# W5500.net
KiCad netlist of a schematic drawn in Altium Designer
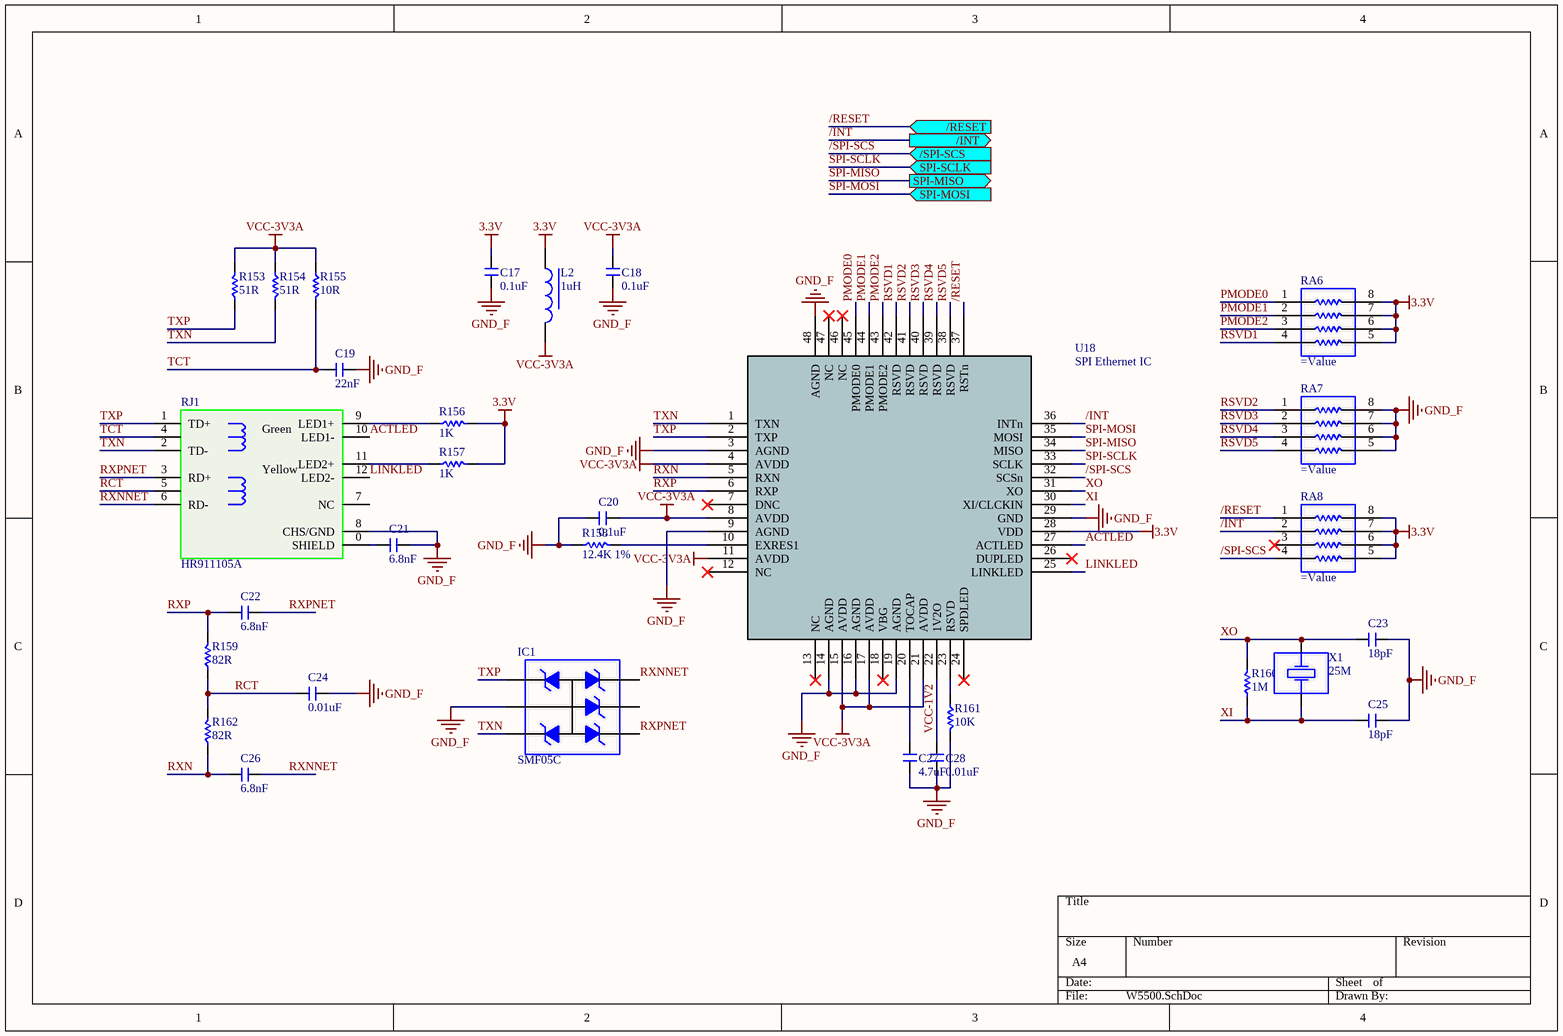
[diagram p0: W5500.SchDoc]

(export (version "E")
  (design (tool "Eeschema 10.0.6"))
  (components
    (comp (ref "C17")
      (value "0.1uF")
      (footprint "C 0805")
      (description "Non-polar patch capacitor")
      (fields (field (name "版权归属") "源创客"))
      (libsource (lib "Passive (Resistor-Capacitor-Inductor-Veristor-Ferrite)") (part "C"))
    )
    (comp (ref "C18")
      (value "0.1uF")
      (footprint "C 0805")
      (description "Non-polar patch capacitor")
      (fields (field (name "版权归属") "源创客"))
      (libsource (lib "Passive (Resistor-Capacitor-Inductor-Veristor-Ferrite)") (part "C"))
    )
    (comp (ref "C19")
      (value "22nF")
      (footprint "C 0805")
      (description "Non-polar patch capacitor")
      (fields (field (name "版权归属") "源创客"))
      (libsource (lib "Passive (Resistor-Capacitor-Inductor-Veristor-Ferrite)") (part "C"))
    )
    (comp (ref "C20")
      (value "0.1uF")
      (footprint "C 0805")
      (description "Non-polar patch capacitor")
      (fields (field (name "版权归属") "源创客"))
      (libsource (lib "Passive (Resistor-Capacitor-Inductor-Veristor-Ferrite)") (part "C"))
    )
    (comp (ref "C21")
      (value "6.8nF")
      (footprint "C 0805")
      (description "Non-polar patch capacitor")
      (fields (field (name "版权归属") "源创客"))
      (libsource (lib "Passive (Resistor-Capacitor-Inductor-Veristor-Ferrite)") (part "C"))
    )
    (comp (ref "C22")
      (value "6.8nF")
      (footprint "C 0805")
      (description "Non-polar patch capacitor")
      (fields (field (name "版权归属") "源创客"))
      (libsource (lib "Passive (Resistor-Capacitor-Inductor-Veristor-Ferrite)") (part "C"))
    )
    (comp (ref "C23")
      (value "18pF")
      (footprint "C 0805")
      (description "Non-polar patch capacitor")
      (fields (field (name "版权归属") "源创客"))
      (libsource (lib "Passive (Resistor-Capacitor-Inductor-Veristor-Ferrite)") (part "C"))
    )
    (comp (ref "C24")
      (value "0.01uF")
      (footprint "C 0805")
      (description "Non-polar patch capacitor")
      (fields (field (name "版权归属") "源创客"))
      (libsource (lib "Passive (Resistor-Capacitor-Inductor-Veristor-Ferrite)") (part "C"))
    )
    (comp (ref "C25")
      (value "18pF")
      (footprint "C 0805")
      (description "Non-polar patch capacitor")
      (fields (field (name "版权归属") "源创客"))
      (libsource (lib "Passive (Resistor-Capacitor-Inductor-Veristor-Ferrite)") (part "C"))
    )
    (comp (ref "C26")
      (value "6.8nF")
      (footprint "C 0805")
      (description "Non-polar patch capacitor")
      (fields (field (name "版权归属") "源创客"))
      (libsource (lib "Passive (Resistor-Capacitor-Inductor-Veristor-Ferrite)") (part "C"))
    )
    (comp (ref "C27")
      (value "4.7uF")
      (footprint "C 0805")
      (description "Non-polar patch capacitor")
      (fields (field (name "版权归属") "源创客"))
      (libsource (lib "Passive (Resistor-Capacitor-Inductor-Veristor-Ferrite)") (part "C"))
    )
    (comp (ref "C28")
      (value "0.01uF")
      (footprint "C 0805")
      (description "Non-polar patch capacitor")
      (fields (field (name "版权归属") "源创客"))
      (libsource (lib "Passive (Resistor-Capacitor-Inductor-Veristor-Ferrite)") (part "C"))
    )
    (comp (ref "IC1")
      (value "SMF05C")
      (footprint "SOT23-6L")
      (description "ESD Protection Diode Array, 5-Line")
      (libsource (lib "Diode-Zener-Rectifier Bridge") (part "SMF05C"))
    )
    (comp (ref "L2")
      (value "1uH")
      (footprint "L 0805")
      (description "Low power chip inductor")
      (fields (field (name "版权归属") "源创客"))
      (libsource (lib "Passive (Resistor-Capacitor-Inductor-Veristor-Ferrite)") (part "L"))
    )
    (comp (ref "R153")
      (value "51R")
      (footprint "R 0805")
      (description "Chip resistor")
      (fields (field (name "版权归属") "源创客"))
      (libsource (lib "Passive (Resistor-Capacitor-Inductor-Veristor-Ferrite)") (part "R"))
    )
    (comp (ref "R154")
      (value "51R")
      (footprint "R 0805")
      (description "Chip resistor")
      (fields (field (name "版权归属") "源创客"))
      (libsource (lib "Passive (Resistor-Capacitor-Inductor-Veristor-Ferrite)") (part "R"))
    )
    (comp (ref "R155")
      (value "10R")
      (footprint "R 0805")
      (description "Chip resistor")
      (fields (field (name "版权归属") "源创客"))
      (libsource (lib "Passive (Resistor-Capacitor-Inductor-Veristor-Ferrite)") (part "R"))
    )
    (comp (ref "R156")
      (value "1K")
      (footprint "R 0805")
      (description "Chip resistor")
      (fields (field (name "版权归属") "源创客"))
      (libsource (lib "Passive (Resistor-Capacitor-Inductor-Veristor-Ferrite)") (part "R"))
    )
    (comp (ref "R157")
      (value "1K")
      (footprint "R 0805")
      (description "Chip resistor")
      (fields (field (name "版权归属") "源创客"))
      (libsource (lib "Passive (Resistor-Capacitor-Inductor-Veristor-Ferrite)") (part "R"))
    )
    (comp (ref "R158")
      (value "12.4K 1%")
      (footprint "R 0805")
      (description "Chip resistor")
      (fields (field (name "版权归属") "源创客"))
      (libsource (lib "Passive (Resistor-Capacitor-Inductor-Veristor-Ferrite)") (part "R"))
    )
    (comp (ref "R159")
      (value "82R")
      (footprint "R 0805")
      (description "Chip resistor")
      (fields (field (name "版权归属") "源创客"))
      (libsource (lib "Passive (Resistor-Capacitor-Inductor-Veristor-Ferrite)") (part "R"))
    )
    (comp (ref "R160")
      (value "1M")
      (footprint "R 0805")
      (description "Chip resistor")
      (fields (field (name "版权归属") "源创客"))
      (libsource (lib "Passive (Resistor-Capacitor-Inductor-Veristor-Ferrite)") (part "R"))
    )
    (comp (ref "R161")
      (value "10K")
      (footprint "R 0805")
      (description "Chip resistor")
      (fields (field (name "版权归属") "源创客"))
      (libsource (lib "Passive (Resistor-Capacitor-Inductor-Veristor-Ferrite)") (part "R"))
    )
    (comp (ref "R162")
      (value "82R")
      (footprint "R 0805")
      (description "Chip resistor")
      (fields (field (name "版权归属") "源创客"))
      (libsource (lib "Passive (Resistor-Capacitor-Inductor-Veristor-Ferrite)") (part "R"))
    )
    (comp (ref "RA6")
      (value "~")
      (footprint "RA1206 (4x0603)")
      (description "4 way Chip Resistor Array")
      (libsource (lib "Passive (Resistor-Capacitor-Inductor-Veristor-Ferrite)") (part "R-ARR"))
    )
    (comp (ref "RA7")
      (value "~")
      (footprint "RA1206 (4x0603)")
      (description "4 way Chip Resistor Array")
      (libsource (lib "Passive (Resistor-Capacitor-Inductor-Veristor-Ferrite)") (part "R-ARR"))
    )
    (comp (ref "RA8")
      (value "~")
      (footprint "RA1206 (4x0603)")
      (description "4 way Chip Resistor Array")
      (libsource (lib "Passive (Resistor-Capacitor-Inductor-Veristor-Ferrite)") (part "R-ARR"))
    )
    (comp (ref "RJ1")
      (value "HR911105A")
      (footprint "RJ-45A12")
      (description "Illuminated Ethernet interface")
      (fields (field (name "版权归属") "源创客"))
      (libsource (lib "IO (Power-USB-Serial-VGA-RJ-Audio-Buzzer)") (part "HR911105A"))
    )
    (comp (ref "U18")
      (value "SPI Ethernet IC")
      (footprint "LQFP48 7X7_L")
      (libsource (lib "Integrated Circuit") (part "W5500"))
    )
    (comp (ref "X1")
      (value "25M")
      (footprint "XTAL-HC49S-THD")
      (description "2-Pin crystal")
      (fields (field (name "版权归属") "源创客"))
      (libsource (lib "Crystal Oscillator") (part "XTAL-2"))
    )
  )
  (nets
    (net (code "1") (name "/ACTLED") (class "Default")
      (node (ref "RJ1") (pin "10") (pinfunction "LED1-_10") (pintype "passive"))
      (node (ref "U18") (pin "27") (pinfunction "ACTLED_27") (pintype "passive"))
    )
    (net (code "2") (name "/LINKLED") (class "Default")
      (node (ref "RJ1") (pin "12") (pinfunction "LED2-_12") (pintype "passive"))
      (node (ref "U18") (pin "25") (pinfunction "LINKLED_25") (pintype "passive"))
    )
    (net (code "3") (name "/PMODE0") (class "Default")
      (node (ref "RA6") (pin "1") (pinfunction "1_1") (pintype "passive"))
      (node (ref "U18") (pin "45") (pinfunction "PMODE0_45") (pintype "passive"))
    )
    (net (code "4") (name "/PMODE1") (class "Default")
      (node (ref "RA6") (pin "2") (pinfunction "2_2") (pintype "passive"))
      (node (ref "U18") (pin "44") (pinfunction "PMODE1_44") (pintype "passive"))
    )
    (net (code "5") (name "/PMODE2") (class "Default")
      (node (ref "RA6") (pin "3") (pinfunction "3_3") (pintype "passive"))
      (node (ref "U18") (pin "43") (pinfunction "PMODE2_43") (pintype "passive"))
    )
    (net (code "6") (name "/RCT") (class "Default")
      (node (ref "C24") (pin "1") (pinfunction "1_1") (pintype "passive"))
      (node (ref "R159") (pin "1") (pinfunction "1_1") (pintype "passive"))
      (node (ref "R162") (pin "2") (pinfunction "2_2") (pintype "passive"))
      (node (ref "RJ1") (pin "5") (pintype "passive"))
    )
    (net (code "7") (name "/RSVD1") (class "Default")
      (node (ref "RA6") (pin "4") (pinfunction "4_4") (pintype "passive"))
      (node (ref "U18") (pin "42") (pinfunction "RSVD_42") (pintype "passive"))
    )
    (net (code "8") (name "/RSVD2") (class "Default")
      (node (ref "RA7") (pin "1") (pinfunction "1_1") (pintype "passive"))
      (node (ref "U18") (pin "41") (pinfunction "RSVD_41") (pintype "passive"))
    )
    (net (code "9") (name "/RSVD3") (class "Default")
      (node (ref "RA7") (pin "2") (pinfunction "2_2") (pintype "passive"))
      (node (ref "U18") (pin "40") (pinfunction "RSVD_40") (pintype "passive"))
    )
    (net (code "10") (name "/RSVD4") (class "Default")
      (node (ref "RA7") (pin "3") (pinfunction "3_3") (pintype "passive"))
      (node (ref "U18") (pin "39") (pinfunction "RSVD_39") (pintype "passive"))
    )
    (net (code "11") (name "/RSVD5") (class "Default")
      (node (ref "RA7") (pin "4") (pinfunction "4_4") (pintype "passive"))
      (node (ref "U18") (pin "38") (pinfunction "RSVD_38") (pintype "passive"))
    )
    (net (code "12") (name "/RXN") (class "Default")
      (node (ref "C26") (pin "1") (pinfunction "1_1") (pintype "passive"))
      (node (ref "R162") (pin "1") (pinfunction "1_1") (pintype "passive"))
      (node (ref "U18") (pin "5") (pinfunction "RXN_5") (pintype "passive"))
    )
    (net (code "13") (name "/RXNNET") (class "Default")
      (node (ref "C26") (pin "2") (pinfunction "2_2") (pintype "passive"))
      (node (ref "IC1") (pin "4") (pinfunction "K_4") (pintype "passive"))
      (node (ref "RJ1") (pin "6") (pinfunction "RD-_6") (pintype "passive"))
    )
    (net (code "14") (name "/RXP") (class "Default")
      (node (ref "C22") (pin "1") (pinfunction "1_1") (pintype "passive"))
      (node (ref "R159") (pin "2") (pinfunction "2_2") (pintype "passive"))
      (node (ref "U18") (pin "6") (pinfunction "RXP_6") (pintype "passive"))
    )
    (net (code "15") (name "/RXPNET") (class "Default")
      (node (ref "C22") (pin "2") (pinfunction "2_2") (pintype "passive"))
      (node (ref "IC1") (pin "6") (pinfunction "K_6") (pintype "passive"))
      (node (ref "RJ1") (pin "3") (pinfunction "RD+_3") (pintype "passive"))
    )
    (net (code "16") (name "/SPI-MISO") (class "Default")
      (node (ref "U18") (pin "34") (pinfunction "MISO_34") (pintype "passive"))
    )
    (net (code "17") (name "/SPI-MOSI") (class "Default")
      (node (ref "U18") (pin "35") (pinfunction "MOSI_35") (pintype "passive"))
    )
    (net (code "18") (name "/SPI-SCLK") (class "Default")
      (node (ref "U18") (pin "33") (pinfunction "SCLK_33") (pintype "passive"))
    )
    (net (code "19") (name "/TCT") (class "Default")
      (node (ref "C19") (pin "1") (pinfunction "1_1") (pintype "passive"))
      (node (ref "R155") (pin "2") (pinfunction "2_2") (pintype "passive"))
      (node (ref "RJ1") (pin "4") (pintype "passive"))
    )
    (net (code "20") (name "/TXN") (class "Default")
      (node (ref "IC1") (pin "3") (pinfunction "K_3") (pintype "passive"))
      (node (ref "R154") (pin "2") (pinfunction "2_2") (pintype "passive"))
      (node (ref "RJ1") (pin "2") (pinfunction "TD-_2") (pintype "passive"))
      (node (ref "U18") (pin "1") (pinfunction "TXN_1") (pintype "passive"))
    )
    (net (code "21") (name "/TXP") (class "Default")
      (node (ref "IC1") (pin "1") (pinfunction "K_1") (pintype "passive"))
      (node (ref "R153") (pin "1") (pinfunction "1_1") (pintype "passive"))
      (node (ref "RJ1") (pin "1") (pinfunction "TD+_1") (pintype "passive"))
      (node (ref "U18") (pin "2") (pinfunction "TXP_2") (pintype "passive"))
    )
    (net (code "22") (name "/VCC-1V2") (class "Default")
      (node (ref "C28") (pin "1") (pinfunction "1_1") (pintype "passive"))
      (node (ref "U18") (pin "22") (pinfunction "1V2O_22") (pintype "passive"))
    )
    (net (code "23") (name "/XI") (class "Default")
      (node (ref "C25") (pin "1") (pinfunction "1_1") (pintype "passive"))
      (node (ref "R160") (pin "1") (pinfunction "1_1") (pintype "passive"))
      (node (ref "U18") (pin "30") (pinfunction "XI/CLCKIN_30") (pintype "passive"))
      (node (ref "X1") (pin "1") (pinfunction "1_1") (pintype "passive"))
    )
    (net (code "24") (name "/XO") (class "Default")
      (node (ref "C23") (pin "1") (pinfunction "1_1") (pintype "passive"))
      (node (ref "R160") (pin "2") (pinfunction "2_2") (pintype "passive"))
      (node (ref "U18") (pin "31") (pinfunction "XO_31") (pintype "passive"))
      (node (ref "X1") (pin "2") (pinfunction "3_2") (pintype "passive"))
    )
    (net (code "25") (name "/{slash}INT") (class "Default")
      (node (ref "RA8") (pin "2") (pinfunction "2_2") (pintype "passive"))
      (node (ref "U18") (pin "36") (pinfunction "INTn_36") (pintype "passive"))
    )
    (net (code "26") (name "/{slash}RESET") (class "Default")
      (node (ref "RA8") (pin "1") (pinfunction "1_1") (pintype "passive"))
      (node (ref "U18") (pin "37") (pinfunction "RSTn_37") (pintype "passive"))
    )
    (net (code "27") (name "/{slash}SPI-SCS") (class "Default")
      (node (ref "RA8") (pin "4") (pinfunction "4_4") (pintype "passive"))
      (node (ref "U18") (pin "32") (pinfunction "SCSn_32") (pintype "passive"))
    )
    (net (code "28") (name "3.3V") (class "Default")
      (node (ref "C17") (pin "2") (pinfunction "2_2") (pintype "passive"))
      (node (ref "L2") (pin "1") (pinfunction "1_1") (pintype "passive"))
      (node (ref "R156") (pin "2") (pinfunction "2_2") (pintype "passive"))
      (node (ref "R157") (pin "2") (pinfunction "2_2") (pintype "passive"))
      (node (ref "RA6") (pin "5") (pinfunction "5_5") (pintype "passive"))
      (node (ref "RA6") (pin "6") (pinfunction "6_6") (pintype "passive"))
      (node (ref "RA6") (pin "7") (pinfunction "7_7") (pintype "passive"))
      (node (ref "RA6") (pin "8") (pinfunction "8_8") (pintype "passive"))
      (node (ref "RA8") (pin "5") (pinfunction "5_5") (pintype "passive"))
      (node (ref "RA8") (pin "6") (pinfunction "6_6") (pintype "passive"))
      (node (ref "RA8") (pin "7") (pinfunction "7_7") (pintype "passive"))
      (node (ref "RA8") (pin "8") (pinfunction "8_8") (pintype "passive"))
      (node (ref "U18") (pin "28") (pinfunction "VDD_28") (pintype "passive"))
    )
    (net (code "29") (name "GND_F") (class "Default")
      (node (ref "C17") (pin "1") (pinfunction "1_1") (pintype "passive"))
      (node (ref "C18") (pin "1") (pinfunction "1_1") (pintype "passive"))
      (node (ref "C19") (pin "2") (pinfunction "2_2") (pintype "passive"))
      (node (ref "C20") (pin "1") (pinfunction "1_1") (pintype "passive"))
      (node (ref "C21") (pin "2") (pinfunction "2_2") (pintype "passive"))
      (node (ref "C23") (pin "2") (pinfunction "2_2") (pintype "passive"))
      (node (ref "C24") (pin "2") (pinfunction "2_2") (pintype "passive"))
      (node (ref "C25") (pin "2") (pinfunction "2_2") (pintype "passive"))
      (node (ref "C27") (pin "2") (pinfunction "2_2") (pintype "passive"))
      (node (ref "C28") (pin "2") (pinfunction "2_2") (pintype "passive"))
      (node (ref "IC1") (pin "2") (pinfunction "A_2") (pintype "passive"))
      (node (ref "R158") (pin "1") (pinfunction "1_1") (pintype "passive"))
      (node (ref "R161") (pin "2") (pinfunction "2_2") (pintype "passive"))
      (node (ref "RA7") (pin "5") (pinfunction "5_5") (pintype "passive"))
      (node (ref "RA7") (pin "6") (pinfunction "6_6") (pintype "passive"))
      (node (ref "RA7") (pin "7") (pinfunction "7_7") (pintype "passive"))
      (node (ref "RA7") (pin "8") (pinfunction "8_8") (pintype "passive"))
      (node (ref "RJ1") (pin "8") (pinfunction "CHS/GND_8") (pintype "passive"))
      (node (ref "U18") (pin "14") (pinfunction "AGND_14") (pintype "passive"))
      (node (ref "U18") (pin "16") (pinfunction "AGND_16") (pintype "passive"))
      (node (ref "U18") (pin "19") (pinfunction "AGND_19") (pintype "passive"))
      (node (ref "U18") (pin "29") (pinfunction "GND_29") (pintype "passive"))
      (node (ref "U18") (pin "3") (pinfunction "AGND_3") (pintype "passive"))
      (node (ref "U18") (pin "48") (pinfunction "AGND_48") (pintype "passive"))
      (node (ref "U18") (pin "9") (pinfunction "AGND_9") (pintype "passive"))
    )
    (net (code "30") (name "Net-(R161-Pad1)") (class "Default")
      (node (ref "R161") (pin "1") (pinfunction "1_1") (pintype "passive"))
      (node (ref "U18") (pin "23") (pinfunction "RSVD_23") (pintype "passive"))
    )
    (net (code "31") (name "Net-(RJ1-LED1+)") (class "Default")
      (node (ref "R156") (pin "1") (pinfunction "1_1") (pintype "passive"))
      (node (ref "RJ1") (pin "9") (pinfunction "LED1+_9") (pintype "passive"))
    )
    (net (code "32") (name "Net-(RJ1-LED2+)") (class "Default")
      (node (ref "R157") (pin "1") (pinfunction "1_1") (pintype "passive"))
      (node (ref "RJ1") (pin "11") (pinfunction "LED2+_11") (pintype "passive"))
    )
    (net (code "33") (name "Net-(RJ1-SHIELD)") (class "Default")
      (node (ref "C21") (pin "1") (pinfunction "1_1") (pintype "passive"))
      (node (ref "RJ1") (pin "0") (pinfunction "SHIELD_0") (pintype "passive"))
    )
    (net (code "34") (name "Net-(U18-EXRES1)") (class "Default")
      (node (ref "R158") (pin "2") (pinfunction "2_2") (pintype "passive"))
      (node (ref "U18") (pin "10") (pinfunction "EXRES1_10") (pintype "passive"))
    )
    (net (code "35") (name "Net-(U18-TOCAP)") (class "Default")
      (node (ref "C27") (pin "1") (pinfunction "1_1") (pintype "passive"))
      (node (ref "U18") (pin "20") (pinfunction "TOCAP_20") (pintype "passive"))
    )
    (net (code "36") (name "VCC-3V3A") (class "Default")
      (node (ref "C18") (pin "2") (pinfunction "2_2") (pintype "passive"))
      (node (ref "C20") (pin "2") (pinfunction "2_2") (pintype "passive"))
      (node (ref "L2") (pin "2") (pinfunction "2_2") (pintype "passive"))
      (node (ref "R153") (pin "2") (pinfunction "2_2") (pintype "passive"))
      (node (ref "R154") (pin "1") (pinfunction "1_1") (pintype "passive"))
      (node (ref "R155") (pin "1") (pinfunction "1_1") (pintype "passive"))
      (node (ref "U18") (pin "11") (pinfunction "AVDD_11") (pintype "passive"))
      (node (ref "U18") (pin "15") (pinfunction "AVDD_15") (pintype "passive"))
      (node (ref "U18") (pin "17") (pinfunction "AVDD_17") (pintype "passive"))
      (node (ref "U18") (pin "21") (pinfunction "AVDD_21") (pintype "passive"))
      (node (ref "U18") (pin "4") (pinfunction "AVDD_4") (pintype "passive"))
      (node (ref "U18") (pin "8") (pinfunction "AVDD_8") (pintype "passive"))
    )
    (net (code "37") (name "unconnected-(IC1-K-Pad5)") (class "Default")
      (node (ref "IC1") (pin "5") (pinfunction "K_5") (pintype "passive"))
    )
    (net (code "38") (name "unconnected-(RA8-Pad3)") (class "Default")
      (node (ref "RA8") (pin "3") (pinfunction "3_3") (pintype "passive+no_connect"))
    )
    (net (code "39") (name "unconnected-(RJ1-NC-Pad7)") (class "Default")
      (node (ref "RJ1") (pin "7") (pinfunction "NC_7") (pintype "passive"))
    )
    (net (code "40") (name "unconnected-(U18-DNC-Pad7)") (class "Default")
      (node (ref "U18") (pin "7") (pinfunction "DNC_7") (pintype "passive+no_connect"))
    )
    (net (code "41") (name "unconnected-(U18-DUPLED-Pad26)") (class "Default")
      (node (ref "U18") (pin "26") (pinfunction "DUPLED_26") (pintype "passive+no_connect"))
    )
    (net (code "42") (name "unconnected-(U18-NC-Pad12)") (class "Default")
      (node (ref "U18") (pin "12") (pinfunction "NC_12") (pintype "passive+no_connect"))
    )
    (net (code "43") (name "unconnected-(U18-NC-Pad13)") (class "Default")
      (node (ref "U18") (pin "13") (pinfunction "NC_13") (pintype "passive+no_connect"))
    )
    (net (code "44") (name "unconnected-(U18-NC-Pad46)") (class "Default")
      (node (ref "U18") (pin "46") (pinfunction "NC_46") (pintype "passive+no_connect"))
    )
    (net (code "45") (name "unconnected-(U18-NC-Pad47)") (class "Default")
      (node (ref "U18") (pin "47") (pinfunction "NC_47") (pintype "passive+no_connect"))
    )
    (net (code "46") (name "unconnected-(U18-SPDLED-Pad24)") (class "Default")
      (node (ref "U18") (pin "24") (pinfunction "SPDLED_24") (pintype "passive+no_connect"))
    )
    (net (code "47") (name "unconnected-(U18-VBG-Pad18)") (class "Default")
      (node (ref "U18") (pin "18") (pinfunction "VBG_18") (pintype "passive+no_connect"))
    )
  )
)
